# USB.net
KiCad netlist of a schematic drawn in Altium Designer
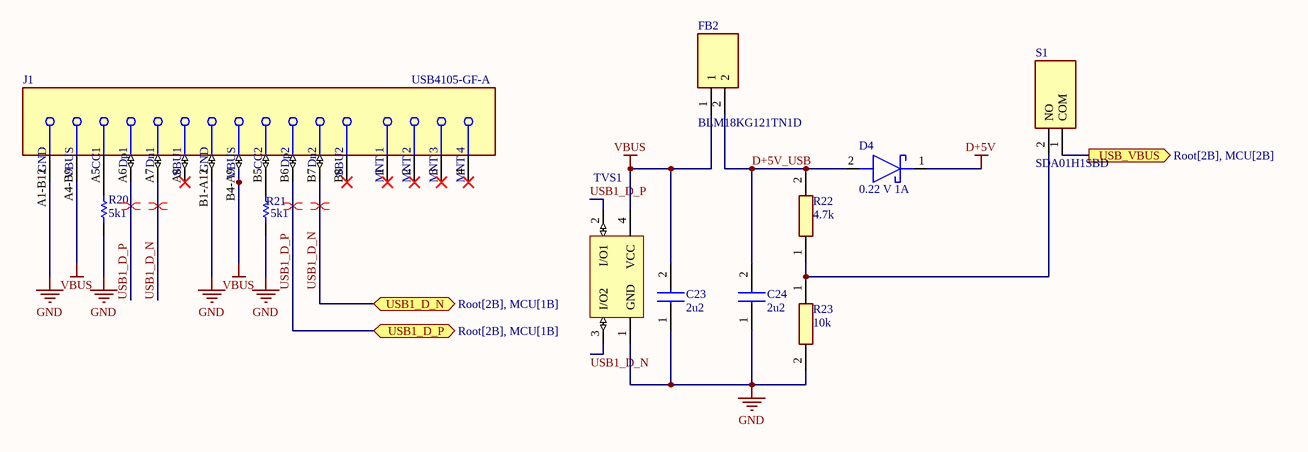
[diagram p0: USB.SchDoc]

(export (version "E")
  (design (tool "Eeschema 10.0.6"))
  (components
    (comp (ref "C23")
      (value "2u2")
      (footprint "SamacSys:CAPC1608X90N")
      (description "CL10B225KP8NNNC")
      (fields (field (name "MOUSER PART NUMBER") "187-CL10B225KP8NNNC"))
      (libsource (lib "*") (part "CL10B225KP8NNNC"))
    )
    (comp (ref "C24")
      (value "2u2")
      (footprint "SamacSys:CAPC1608X90N")
      (description "CL10B225KP8NNNC")
      (fields (field (name "MOUSER PART NUMBER") "187-CL10B225KP8NNNC"))
      (libsource (lib "*") (part "CL10B225KP8NNNC"))
    )
    (comp (ref "D4")
      (value "0.22 V 1A")
      (footprint "SamacSys:DIOM5436X330N")
      (description "LSM115JE3_TR13")
      (fields
        (field (name "MANUFACTURER_PART_NUMBER") "LSM115JE3/TR13")
        (field (name "MOUSER PART NUMBER") "494-LSM115JE3/TR13")
      )
      (libsource (lib "*") (part "LSM115JE3_TR13"))
    )
    (comp (ref "FB2")
      (value "BLM18KG121TN1D")
      (footprint "SamacSys:BLM18EG101TH1D")
      (description "Ferrite Bead")
      (fields (field (name "MOUSER PART NUMBER") "81-BLM18KG121TN1D"))
      (libsource (lib "SamacSys") (part "BLM18KG121TN1D"))
    )
    (comp (ref "J1")
      (value "USB4105-GF-A")
      (footprint "FP-USB4105-GF-A-MFG")
      (description "CONN RCPT USB2.0 TYPEC 5A")
      (fields
        (field (name "MANUFACTURER") "GCT")
        (field (name "OCTOPART") "https://octopart.com/usb4105-gf-a-gct-106627878")
      )
      (libsource (lib "Altium Content Vault") (part "e7c17a616881a82b79941196b4bec10"))
    )
    (comp (ref "R20")
      (value "ERA-6AEB103V")
      (footprint "RESC2013X60X40LL20T25_A")
      (fields
        (field (name "TOLERANCE") "0.1%")
        (field (name "RESISTANCE") "5k1")
        (field (name "MANUFACTURER") "Panasonic")
      )
      (libsource (lib "Altium Content Vault") (part "RES-2"))
    )
    (comp (ref "R21")
      (value "ERA-6AEB103V")
      (footprint "RESC2013X60X40LL20T25_A")
      (fields
        (field (name "TOLERANCE") "0.1%")
        (field (name "RESISTANCE") "5k1")
        (field (name "MANUFACTURER") "Panasonic")
      )
      (libsource (lib "Altium Content Vault") (part "RES-2"))
    )
    (comp (ref "R22")
      (value "4.7k")
      (footprint "SamacSys:RESC1608X55N")
      (description "RC0603FR-074K7L")
      (fields (field (name "MOUSER PART NUMBER") "603-RC0603FR-074K7L"))
      (libsource (lib "SamacSys") (part "RC0603FR-074K7L"))
    )
    (comp (ref "R23")
      (value "10k")
      (footprint "SamacSys:RESC1608X55N")
      (description "RC0603FR0710KL")
      (libsource (lib "*") (part "RC0603FR0710KL"))
    )
    (comp (ref "S1")
      (value "SDA01H1SBD")
      (footprint "SamacSys:SDA01H1SBD")
      (description "Switch")
      (fields (field (name "MOUSER PART NUMBER") "611-SDA01H1SBD"))
      (libsource (lib "*") (part "SDA01H1SBD"))
    )
    (comp (ref "TVS1")
      (value "PRTR5V0U2X,215")
      (footprint "NXP-SOT143B-4_V")
      (fields (field (name "MANUFACTURER") "NXP Semiconductors"))
      (libsource (lib "Altium Content Vault") (part "NXP-PRTR5V0U2X,215-4"))
    )
  )
  (nets
    (net (code "1") (name "/D+5V_USB") (class "Default")
      (node (ref "C24") (pin "2") (pinfunction "2_2") (pintype "passive"))
      (node (ref "D4") (pin "2") (pinfunction "A_2") (pintype "passive"))
      (node (ref "FB2") (pin "2") (pinfunction "2_2") (pintype "passive"))
      (node (ref "R22") (pin "2") (pinfunction "2_2") (pintype "passive"))
    )
    (net (code "2") (name "/USB1_D_N") (class "Default")
      (node (ref "J1") (pin "A7") (pinfunction "Dn1_A7") (pintype "bidirectional"))
      (node (ref "J1") (pin "B7") (pinfunction "Dn2_B7") (pintype "bidirectional"))
      (node (ref "TVS1") (pin "3") (pinfunction "I/O2_3") (pintype "bidirectional"))
    )
    (net (code "3") (name "/USB1_D_P") (class "Default")
      (node (ref "J1") (pin "A6") (pinfunction "Dp1_A6") (pintype "bidirectional"))
      (node (ref "J1") (pin "B6") (pinfunction "Dp2_B6") (pintype "bidirectional"))
      (node (ref "TVS1") (pin "2") (pinfunction "I/O1_2") (pintype "bidirectional"))
    )
    (net (code "4") (name "/USB_VBUS") (class "Default")
      (node (ref "S1") (pin "1") (pinfunction "COM_1") (pintype "passive"))
    )
    (net (code "5") (name "D+5V") (class "Default")
      (node (ref "D4") (pin "1") (pinfunction "K_1") (pintype "passive"))
    )
    (net (code "6") (name "GND") (class "Default")
      (node (ref "C23") (pin "1") (pinfunction "1_1") (pintype "passive"))
      (node (ref "C24") (pin "1") (pinfunction "1_1") (pintype "passive"))
      (node (ref "J1") (pin "A1-B12") (pinfunction "GND_A1-B12") (pintype "power_in"))
      (node (ref "J1") (pin "B1-A12") (pinfunction "GND_B1-A12") (pintype "bidirectional"))
      (node (ref "R20") (pin "1") (pinfunction "1_1") (pintype "passive"))
      (node (ref "R21") (pin "1") (pinfunction "1_1") (pintype "passive"))
      (node (ref "R23") (pin "2") (pinfunction "2_2") (pintype "passive"))
      (node (ref "TVS1") (pin "1") (pinfunction "GND_1") (pintype "power_in"))
    )
    (net (code "7") (name "Net-(J1-CC1)") (class "Default")
      (node (ref "J1") (pin "A5") (pinfunction "CC1_A5") (pintype "power_in"))
      (node (ref "R20") (pin "2") (pinfunction "2_2") (pintype "passive"))
    )
    (net (code "8") (name "Net-(J1-CC2)") (class "Default")
      (node (ref "J1") (pin "B5") (pinfunction "CC2_B5") (pintype "bidirectional"))
      (node (ref "R21") (pin "2") (pinfunction "2_2") (pintype "passive"))
    )
    (net (code "9") (name "Net-(S1-NO)") (class "Default")
      (node (ref "R22") (pin "1") (pinfunction "1_1") (pintype "passive"))
      (node (ref "R23") (pin "1") (pinfunction "1_1") (pintype "passive"))
      (node (ref "S1") (pin "2") (pinfunction "NO_2") (pintype "passive"))
    )
    (net (code "10") (name "VBUS") (class "Default")
      (node (ref "C23") (pin "2") (pinfunction "2_2") (pintype "passive"))
      (node (ref "FB2") (pin "1") (pinfunction "1_1") (pintype "passive"))
      (node (ref "J1") (pin "A4-B9") (pinfunction "VBUS_A4-B9") (pintype "power_in"))
      (node (ref "J1") (pin "B4-A9") (pinfunction "VBUS_B4-A9") (pintype "bidirectional"))
      (node (ref "TVS1") (pin "4") (pinfunction "VCC_4") (pintype "power_in"))
    )
    (net (code "11") (name "unconnected-(J1-MNT_1-Pad1)") (class "Default")
      (node (ref "J1") (pin "1") (pinfunction "MNT_1_1") (pintype "power_in+no_connect"))
    )
    (net (code "12") (name "unconnected-(J1-MNT_2-Pad2)") (class "Default")
      (node (ref "J1") (pin "2") (pinfunction "MNT_2_2") (pintype "power_in+no_connect"))
    )
    (net (code "13") (name "unconnected-(J1-MNT_3-Pad3)") (class "Default")
      (node (ref "J1") (pin "3") (pinfunction "MNT_3_3") (pintype "power_in+no_connect"))
    )
    (net (code "14") (name "unconnected-(J1-MNT_4-Pad4)") (class "Default")
      (node (ref "J1") (pin "4") (pinfunction "MNT_4_4") (pintype "power_in+no_connect"))
    )
    (net (code "15") (name "unconnected-(J1-SBU1-PadA8)") (class "Default")
      (node (ref "J1") (pin "A8") (pinfunction "SBU1_A8") (pintype "bidirectional+no_connect"))
    )
    (net (code "16") (name "unconnected-(J1-SBU2-PadB8)") (class "Default")
      (node (ref "J1") (pin "B8") (pinfunction "SBU2_B8") (pintype "power_in+no_connect"))
    )
  )
)
